# LissajousRevA.net
KiCad netlist of a schematic drawn in EAGLE
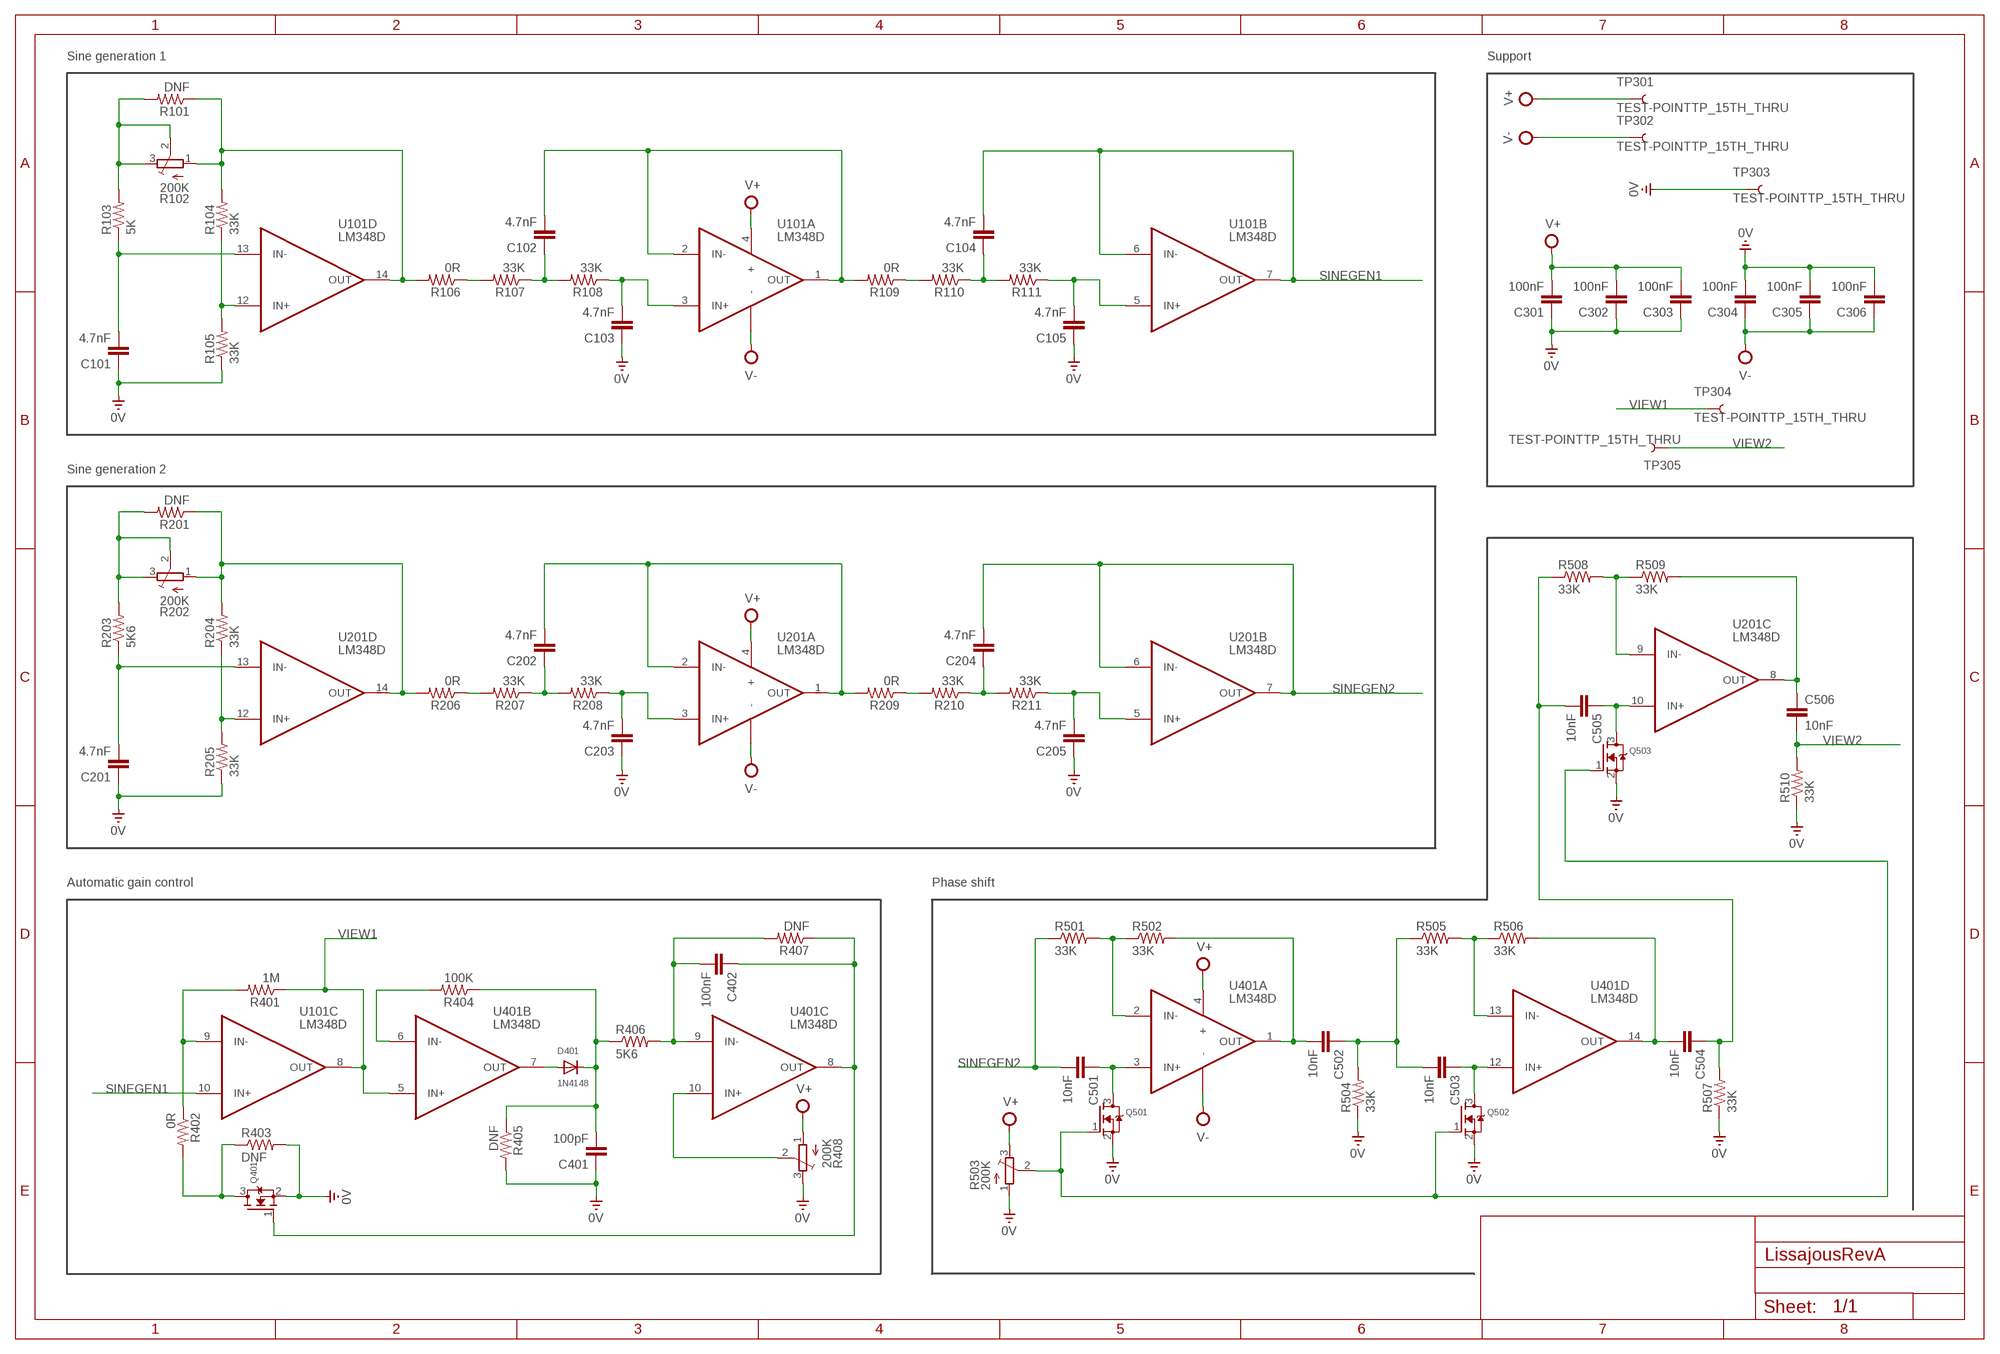
[diagram p0: schematic, sheet 1]

(export (version "E")
  (design (tool "Eeschema 10.0.6"))
  (components
    (comp (ref "C101")
      (value "4.7nF")
      (footprint "eagle-import:0603-CAP")
      (libsource (lib "eagle-import") (part "CAP0603-CAP"))
    )
    (comp (ref "C102")
      (value "4.7nF")
      (footprint "eagle-import:0603-CAP")
      (libsource (lib "eagle-import") (part "CAP0603-CAP"))
    )
    (comp (ref "C103")
      (value "4.7nF")
      (footprint "eagle-import:0603-CAP")
      (libsource (lib "eagle-import") (part "CAP0603-CAP"))
    )
    (comp (ref "C104")
      (value "4.7nF")
      (footprint "eagle-import:0603-CAP")
      (libsource (lib "eagle-import") (part "CAP0603-CAP"))
    )
    (comp (ref "C105")
      (value "4.7nF")
      (footprint "eagle-import:0603-CAP")
      (libsource (lib "eagle-import") (part "CAP0603-CAP"))
    )
    (comp (ref "C201")
      (value "4.7nF")
      (footprint "eagle-import:0603-CAP")
      (libsource (lib "eagle-import") (part "CAP0603-CAP"))
    )
    (comp (ref "C202")
      (value "4.7nF")
      (footprint "eagle-import:0603-CAP")
      (libsource (lib "eagle-import") (part "CAP0603-CAP"))
    )
    (comp (ref "C203")
      (value "4.7nF")
      (footprint "eagle-import:0603-CAP")
      (libsource (lib "eagle-import") (part "CAP0603-CAP"))
    )
    (comp (ref "C204")
      (value "4.7nF")
      (footprint "eagle-import:0603-CAP")
      (libsource (lib "eagle-import") (part "CAP0603-CAP"))
    )
    (comp (ref "C205")
      (value "4.7nF")
      (footprint "eagle-import:0603-CAP")
      (libsource (lib "eagle-import") (part "CAP0603-CAP"))
    )
    (comp (ref "C301")
      (value "100nF")
      (footprint "eagle-import:0603-CAP")
      (libsource (lib "eagle-import") (part "CAP0603-CAP"))
    )
    (comp (ref "C302")
      (value "100nF")
      (footprint "eagle-import:0603-CAP")
      (libsource (lib "eagle-import") (part "CAP0603-CAP"))
    )
    (comp (ref "C303")
      (value "100nF")
      (footprint "eagle-import:0603-CAP")
      (libsource (lib "eagle-import") (part "CAP0603-CAP"))
    )
    (comp (ref "C304")
      (value "100nF")
      (footprint "eagle-import:0603-CAP")
      (libsource (lib "eagle-import") (part "CAP0603-CAP"))
    )
    (comp (ref "C305")
      (value "100nF")
      (footprint "eagle-import:0603-CAP")
      (libsource (lib "eagle-import") (part "CAP0603-CAP"))
    )
    (comp (ref "C306")
      (value "100nF")
      (footprint "eagle-import:0603-CAP")
      (libsource (lib "eagle-import") (part "CAP0603-CAP"))
    )
    (comp (ref "C401")
      (value "100pF")
      (footprint "eagle-import:0603-CAP")
      (libsource (lib "eagle-import") (part "CAP0603-CAP"))
    )
    (comp (ref "C402")
      (value "100nF")
      (footprint "eagle-import:0603-CAP")
      (libsource (lib "eagle-import") (part "CAP0603-CAP"))
    )
    (comp (ref "C501")
      (value "10nF")
      (footprint "eagle-import:0603-CAP")
      (libsource (lib "eagle-import") (part "CAP0603-CAP"))
    )
    (comp (ref "C502")
      (value "10nF")
      (footprint "eagle-import:0603-CAP")
      (libsource (lib "eagle-import") (part "CAP0603-CAP"))
    )
    (comp (ref "C503")
      (value "10nF")
      (footprint "eagle-import:0603-CAP")
      (libsource (lib "eagle-import") (part "CAP0603-CAP"))
    )
    (comp (ref "C504")
      (value "10nF")
      (footprint "eagle-import:0603-CAP")
      (libsource (lib "eagle-import") (part "CAP0603-CAP"))
    )
    (comp (ref "C505")
      (value "10nF")
      (footprint "eagle-import:0603-CAP")
      (libsource (lib "eagle-import") (part "CAP0603-CAP"))
    )
    (comp (ref "C506")
      (value "10nF")
      (footprint "eagle-import:0603-CAP")
      (libsource (lib "eagle-import") (part "CAP0603-CAP"))
    )
    (comp (ref "D401")
      (value "1N4148")
      (footprint "eagle-import:SMADIODE")
      (libsource (lib "eagle-import") (part "DIODESMA"))
    )
    (comp (ref "Q401")
      (value "MOSFET-NREFLOW")
      (footprint "eagle-import:SOT23")
      (libsource (lib "eagle-import") (part "MOSFET-NREFLOW"))
    )
    (comp (ref "Q501")
      (value "MOSFET-NREFLOW")
      (footprint "eagle-import:SOT23")
      (libsource (lib "eagle-import") (part "MOSFET-NREFLOW"))
    )
    (comp (ref "Q502")
      (value "MOSFET-NREFLOW")
      (footprint "eagle-import:SOT23")
      (libsource (lib "eagle-import") (part "MOSFET-NREFLOW"))
    )
    (comp (ref "Q503")
      (value "MOSFET-NREFLOW")
      (footprint "eagle-import:SOT23")
      (libsource (lib "eagle-import") (part "MOSFET-NREFLOW"))
    )
    (comp (ref "R101")
      (value "DNF")
      (footprint "eagle-import:0603-RES")
      (libsource (lib "eagle-import") (part "RESISTOR0603-RES"))
    )
    (comp (ref "R102")
      (value "200K")
      (footprint "eagle-import:TC33X")
      (libsource (lib "eagle-import") (part "TRIMPOTTC33X"))
    )
    (comp (ref "R103")
      (value "5K")
      (footprint "eagle-import:0603-RES")
      (libsource (lib "eagle-import") (part "RESISTOR0603-RES"))
    )
    (comp (ref "R104")
      (value "33K")
      (footprint "eagle-import:0603-RES")
      (libsource (lib "eagle-import") (part "RESISTOR0603-RES"))
    )
    (comp (ref "R105")
      (value "33K")
      (footprint "eagle-import:0603-RES")
      (libsource (lib "eagle-import") (part "RESISTOR0603-RES"))
    )
    (comp (ref "R106")
      (value "0R")
      (footprint "eagle-import:0603-RES")
      (libsource (lib "eagle-import") (part "RESISTOR0603-RES"))
    )
    (comp (ref "R107")
      (value "33K")
      (footprint "eagle-import:0603-RES")
      (libsource (lib "eagle-import") (part "RESISTOR0603-RES"))
    )
    (comp (ref "R108")
      (value "33K")
      (footprint "eagle-import:0603-RES")
      (libsource (lib "eagle-import") (part "RESISTOR0603-RES"))
    )
    (comp (ref "R109")
      (value "0R")
      (footprint "eagle-import:0603-RES")
      (libsource (lib "eagle-import") (part "RESISTOR0603-RES"))
    )
    (comp (ref "R110")
      (value "33K")
      (footprint "eagle-import:0603-RES")
      (libsource (lib "eagle-import") (part "RESISTOR0603-RES"))
    )
    (comp (ref "R111")
      (value "33K")
      (footprint "eagle-import:0603-RES")
      (libsource (lib "eagle-import") (part "RESISTOR0603-RES"))
    )
    (comp (ref "R201")
      (value "DNF")
      (footprint "eagle-import:0603-RES")
      (libsource (lib "eagle-import") (part "RESISTOR0603-RES"))
    )
    (comp (ref "R202")
      (value "200K")
      (footprint "eagle-import:TC33X")
      (libsource (lib "eagle-import") (part "TRIMPOTTC33X"))
    )
    (comp (ref "R203")
      (value "5K6")
      (footprint "eagle-import:0603-RES")
      (libsource (lib "eagle-import") (part "RESISTOR0603-RES"))
    )
    (comp (ref "R204")
      (value "33K")
      (footprint "eagle-import:0603-RES")
      (libsource (lib "eagle-import") (part "RESISTOR0603-RES"))
    )
    (comp (ref "R205")
      (value "33K")
      (footprint "eagle-import:0603-RES")
      (libsource (lib "eagle-import") (part "RESISTOR0603-RES"))
    )
    (comp (ref "R206")
      (value "0R")
      (footprint "eagle-import:0603-RES")
      (libsource (lib "eagle-import") (part "RESISTOR0603-RES"))
    )
    (comp (ref "R207")
      (value "33K")
      (footprint "eagle-import:0603-RES")
      (libsource (lib "eagle-import") (part "RESISTOR0603-RES"))
    )
    (comp (ref "R208")
      (value "33K")
      (footprint "eagle-import:0603-RES")
      (libsource (lib "eagle-import") (part "RESISTOR0603-RES"))
    )
    (comp (ref "R209")
      (value "0R")
      (footprint "eagle-import:0603-RES")
      (libsource (lib "eagle-import") (part "RESISTOR0603-RES"))
    )
    (comp (ref "R210")
      (value "33K")
      (footprint "eagle-import:0603-RES")
      (libsource (lib "eagle-import") (part "RESISTOR0603-RES"))
    )
    (comp (ref "R211")
      (value "33K")
      (footprint "eagle-import:0603-RES")
      (libsource (lib "eagle-import") (part "RESISTOR0603-RES"))
    )
    (comp (ref "R401")
      (value "1M")
      (footprint "eagle-import:0603-RES")
      (libsource (lib "eagle-import") (part "RESISTOR0603-RES"))
    )
    (comp (ref "R402")
      (value "0R")
      (footprint "eagle-import:0603-RES")
      (libsource (lib "eagle-import") (part "RESISTOR0603-RES"))
    )
    (comp (ref "R403")
      (value "DNF")
      (footprint "eagle-import:0603-RES")
      (libsource (lib "eagle-import") (part "RESISTOR0603-RES"))
    )
    (comp (ref "R404")
      (value "100K")
      (footprint "eagle-import:0603-RES")
      (libsource (lib "eagle-import") (part "RESISTOR0603-RES"))
    )
    (comp (ref "R405")
      (value "DNF")
      (footprint "eagle-import:0603-RES")
      (libsource (lib "eagle-import") (part "RESISTOR0603-RES"))
    )
    (comp (ref "R406")
      (value "5K6")
      (footprint "eagle-import:0603-RES")
      (libsource (lib "eagle-import") (part "RESISTOR0603-RES"))
    )
    (comp (ref "R407")
      (value "DNF")
      (footprint "eagle-import:0603-RES")
      (libsource (lib "eagle-import") (part "RESISTOR0603-RES"))
    )
    (comp (ref "R408")
      (value "200K")
      (footprint "eagle-import:TC33X")
      (libsource (lib "eagle-import") (part "TRIMPOTTC33X"))
    )
    (comp (ref "R501")
      (value "33K")
      (footprint "eagle-import:0603-RES")
      (libsource (lib "eagle-import") (part "RESISTOR0603-RES"))
    )
    (comp (ref "R502")
      (value "33K")
      (footprint "eagle-import:0603-RES")
      (libsource (lib "eagle-import") (part "RESISTOR0603-RES"))
    )
    (comp (ref "R503")
      (value "200K")
      (footprint "eagle-import:TC33X")
      (libsource (lib "eagle-import") (part "TRIMPOTTC33X"))
    )
    (comp (ref "R504")
      (value "33K")
      (footprint "eagle-import:0603-RES")
      (libsource (lib "eagle-import") (part "RESISTOR0603-RES"))
    )
    (comp (ref "R505")
      (value "33K")
      (footprint "eagle-import:0603-RES")
      (libsource (lib "eagle-import") (part "RESISTOR0603-RES"))
    )
    (comp (ref "R506")
      (value "33K")
      (footprint "eagle-import:0603-RES")
      (libsource (lib "eagle-import") (part "RESISTOR0603-RES"))
    )
    (comp (ref "R507")
      (value "33K")
      (footprint "eagle-import:0603-RES")
      (libsource (lib "eagle-import") (part "RESISTOR0603-RES"))
    )
    (comp (ref "R508")
      (value "33K")
      (footprint "eagle-import:0603-RES")
      (libsource (lib "eagle-import") (part "RESISTOR0603-RES"))
    )
    (comp (ref "R509")
      (value "33K")
      (footprint "eagle-import:0603-RES")
      (libsource (lib "eagle-import") (part "RESISTOR0603-RES"))
    )
    (comp (ref "R510")
      (value "33K")
      (footprint "eagle-import:0603-RES")
      (libsource (lib "eagle-import") (part "RESISTOR0603-RES"))
    )
    (comp (ref "TP301")
      (value "TEST-POINTTP_15TH_THRU")
      (footprint "eagle-import:TP_15TH")
      (libsource (lib "eagle-import") (part "TEST-POINTTP_15TH_THRU"))
    )
    (comp (ref "TP302")
      (value "TEST-POINTTP_15TH_THRU")
      (footprint "eagle-import:TP_15TH")
      (libsource (lib "eagle-import") (part "TEST-POINTTP_15TH_THRU"))
    )
    (comp (ref "TP303")
      (value "TEST-POINTTP_15TH_THRU")
      (footprint "eagle-import:TP_15TH")
      (libsource (lib "eagle-import") (part "TEST-POINTTP_15TH_THRU"))
    )
    (comp (ref "TP304")
      (value "TEST-POINTTP_15TH_THRU")
      (footprint "eagle-import:TP_15TH")
      (libsource (lib "eagle-import") (part "TEST-POINTTP_15TH_THRU"))
    )
    (comp (ref "TP305")
      (value "TEST-POINTTP_15TH_THRU")
      (footprint "eagle-import:TP_15TH")
      (libsource (lib "eagle-import") (part "TEST-POINTTP_15TH_THRU"))
    )
    (comp (ref "U101")
      (value "LM348D")
      (footprint "eagle-import:SOIC127P600X175-14N")
      (libsource (lib "eagle-import") (part "LM348D"))
    )
    (comp (ref "U201")
      (value "LM348D")
      (footprint "eagle-import:SOIC127P600X175-14N")
      (libsource (lib "eagle-import") (part "LM348D"))
    )
    (comp (ref "U401")
      (value "LM348D")
      (footprint "eagle-import:SOIC127P600X175-14N")
      (libsource (lib "eagle-import") (part "LM348D"))
    )
  )
  (nets
    (net (code "1") (name "/SINEGEN1") (class "Default")
      (node (ref "C104") (pin "2") (pinfunction "2_2") (pintype "passive"))
      (node (ref "U101") (pin "10") (pinfunction "IN+_10") (pintype "output"))
      (node (ref "U101") (pin "6") (pinfunction "IN-_6") (pintype "output"))
      (node (ref "U101") (pin "7") (pinfunction "OUT_7") (pintype "output"))
    )
    (net (code "2") (name "/SINEGEN2") (class "Default")
      (node (ref "C204") (pin "2") (pinfunction "2_2") (pintype "passive"))
      (node (ref "C501") (pin "2") (pinfunction "2_2") (pintype "passive"))
      (node (ref "R501") (pin "1") (pinfunction "1_1") (pintype "passive"))
      (node (ref "U201") (pin "6") (pinfunction "IN-_6") (pintype "output"))
      (node (ref "U201") (pin "7") (pinfunction "OUT_7") (pintype "output"))
    )
    (net (code "3") (name "/VIEW1") (class "Default")
      (node (ref "R401") (pin "1") (pinfunction "1_1") (pintype "passive"))
      (node (ref "TP304") (pin "P$1") (pinfunction "1_P$1") (pintype "bidirectional"))
      (node (ref "U101") (pin "8") (pinfunction "OUT_8") (pintype "output"))
      (node (ref "U401") (pin "5") (pinfunction "IN+_5") (pintype "output"))
    )
    (net (code "4") (name "/VIEW2") (class "Default")
      (node (ref "C506") (pin "2") (pinfunction "2_2") (pintype "passive"))
      (node (ref "R510") (pin "2") (pinfunction "2_2") (pintype "passive"))
      (node (ref "TP305") (pin "P$1") (pinfunction "1_P$1") (pintype "bidirectional"))
    )
    (net (code "5") (name "0V") (class "Default")
      (node (ref "C101") (pin "1") (pinfunction "1_1") (pintype "passive"))
      (node (ref "C103") (pin "1") (pinfunction "1_1") (pintype "passive"))
      (node (ref "C105") (pin "1") (pinfunction "1_1") (pintype "passive"))
      (node (ref "C201") (pin "1") (pinfunction "1_1") (pintype "passive"))
      (node (ref "C203") (pin "1") (pinfunction "1_1") (pintype "passive"))
      (node (ref "C205") (pin "1") (pinfunction "1_1") (pintype "passive"))
      (node (ref "C301") (pin "1") (pinfunction "1_1") (pintype "passive"))
      (node (ref "C302") (pin "1") (pinfunction "1_1") (pintype "passive"))
      (node (ref "C303") (pin "1") (pinfunction "1_1") (pintype "passive"))
      (node (ref "C304") (pin "2") (pinfunction "2_2") (pintype "passive"))
      (node (ref "C305") (pin "2") (pinfunction "2_2") (pintype "passive"))
      (node (ref "C306") (pin "2") (pinfunction "2_2") (pintype "passive"))
      (node (ref "C401") (pin "1") (pinfunction "1_1") (pintype "passive"))
      (node (ref "Q401") (pin "2") (pinfunction "S_2") (pintype "bidirectional"))
      (node (ref "Q501") (pin "2") (pinfunction "S_2") (pintype "bidirectional"))
      (node (ref "Q502") (pin "2") (pinfunction "S_2") (pintype "bidirectional"))
      (node (ref "Q503") (pin "2") (pinfunction "S_2") (pintype "bidirectional"))
      (node (ref "R105") (pin "1") (pinfunction "1_1") (pintype "passive"))
      (node (ref "R205") (pin "1") (pinfunction "1_1") (pintype "passive"))
      (node (ref "R403") (pin "2") (pinfunction "2_2") (pintype "passive"))
      (node (ref "R405") (pin "2") (pinfunction "2_2") (pintype "passive"))
      (node (ref "R408") (pin "3") (pinfunction "E_3") (pintype "passive"))
      (node (ref "R503") (pin "1") (pinfunction "A_1") (pintype "passive"))
      (node (ref "R504") (pin "1") (pinfunction "1_1") (pintype "passive"))
      (node (ref "R507") (pin "1") (pinfunction "1_1") (pintype "passive"))
      (node (ref "R510") (pin "1") (pinfunction "1_1") (pintype "passive"))
      (node (ref "TP303") (pin "P$1") (pinfunction "1_P$1") (pintype "bidirectional"))
    )
    (net (code "6") (name "Net-(C102-Pad1)") (class "Default")
      (node (ref "C102") (pin "1") (pinfunction "1_1") (pintype "passive"))
      (node (ref "R107") (pin "1") (pinfunction "1_1") (pintype "passive"))
      (node (ref "R108") (pin "2") (pinfunction "2_2") (pintype "passive"))
    )
    (net (code "7") (name "Net-(C104-Pad1)") (class "Default")
      (node (ref "C104") (pin "1") (pinfunction "1_1") (pintype "passive"))
      (node (ref "R110") (pin "1") (pinfunction "1_1") (pintype "passive"))
      (node (ref "R111") (pin "2") (pinfunction "2_2") (pintype "passive"))
    )
    (net (code "8") (name "Net-(C202-Pad1)") (class "Default")
      (node (ref "C202") (pin "1") (pinfunction "1_1") (pintype "passive"))
      (node (ref "R207") (pin "1") (pinfunction "1_1") (pintype "passive"))
      (node (ref "R208") (pin "2") (pinfunction "2_2") (pintype "passive"))
    )
    (net (code "9") (name "Net-(C204-Pad1)") (class "Default")
      (node (ref "C204") (pin "1") (pinfunction "1_1") (pintype "passive"))
      (node (ref "R210") (pin "1") (pinfunction "1_1") (pintype "passive"))
      (node (ref "R211") (pin "2") (pinfunction "2_2") (pintype "passive"))
    )
    (net (code "10") (name "Net-(C401-Pad2)") (class "Default")
      (node (ref "C401") (pin "2") (pinfunction "2_2") (pintype "passive"))
      (node (ref "D401") (pin "C") (pinfunction "C_C") (pintype "passive"))
      (node (ref "R404") (pin "1") (pinfunction "1_1") (pintype "passive"))
      (node (ref "R405") (pin "1") (pinfunction "1_1") (pintype "passive"))
      (node (ref "R406") (pin "1") (pinfunction "1_1") (pintype "passive"))
    )
    (net (code "11") (name "Net-(C502-Pad1)") (class "Default")
      (node (ref "C502") (pin "1") (pinfunction "1_1") (pintype "passive"))
      (node (ref "C503") (pin "2") (pinfunction "2_2") (pintype "passive"))
      (node (ref "R504") (pin "2") (pinfunction "2_2") (pintype "passive"))
      (node (ref "R505") (pin "1") (pinfunction "1_1") (pintype "passive"))
    )
    (net (code "12") (name "Net-(C504-Pad1)") (class "Default")
      (node (ref "C504") (pin "1") (pinfunction "1_1") (pintype "passive"))
      (node (ref "C505") (pin "2") (pinfunction "2_2") (pintype "passive"))
      (node (ref "R507") (pin "2") (pinfunction "2_2") (pintype "passive"))
      (node (ref "R508") (pin "1") (pinfunction "1_1") (pintype "passive"))
    )
    (net (code "13") (name "Net-(Q401-D)") (class "Default")
      (node (ref "Q401") (pin "3") (pinfunction "D_3") (pintype "bidirectional"))
      (node (ref "R402") (pin "2") (pinfunction "2_2") (pintype "passive"))
      (node (ref "R403") (pin "1") (pinfunction "1_1") (pintype "passive"))
    )
    (net (code "14") (name "Net-(Q401-G)") (class "Default")
      (node (ref "C402") (pin "1") (pinfunction "1_1") (pintype "passive"))
      (node (ref "Q401") (pin "1") (pinfunction "G_1") (pintype "bidirectional"))
      (node (ref "R407") (pin "1") (pinfunction "1_1") (pintype "passive"))
      (node (ref "U401") (pin "8") (pinfunction "OUT_8") (pintype "output"))
    )
    (net (code "15") (name "Net-(Q501-D)") (class "Default")
      (node (ref "C501") (pin "1") (pinfunction "1_1") (pintype "passive"))
      (node (ref "Q501") (pin "3") (pinfunction "D_3") (pintype "bidirectional"))
      (node (ref "U401") (pin "3") (pinfunction "IN+_3") (pintype "output"))
    )
    (net (code "16") (name "Net-(Q501-G)") (class "Default")
      (node (ref "Q501") (pin "1") (pinfunction "G_1") (pintype "bidirectional"))
      (node (ref "Q502") (pin "1") (pinfunction "G_1") (pintype "bidirectional"))
      (node (ref "Q503") (pin "1") (pinfunction "G_1") (pintype "bidirectional"))
      (node (ref "R503") (pin "2") (pinfunction "S_2") (pintype "passive"))
    )
    (net (code "17") (name "Net-(Q502-D)") (class "Default")
      (node (ref "C503") (pin "1") (pinfunction "1_1") (pintype "passive"))
      (node (ref "Q502") (pin "3") (pinfunction "D_3") (pintype "bidirectional"))
      (node (ref "U401") (pin "12") (pinfunction "IN+_12") (pintype "output"))
    )
    (net (code "18") (name "Net-(Q503-D)") (class "Default")
      (node (ref "C505") (pin "1") (pinfunction "1_1") (pintype "passive"))
      (node (ref "Q503") (pin "3") (pinfunction "D_3") (pintype "bidirectional"))
      (node (ref "U201") (pin "10") (pinfunction "IN+_10") (pintype "output"))
    )
    (net (code "19") (name "Net-(R102-A)") (class "Default")
      (node (ref "R101") (pin "1") (pinfunction "1_1") (pintype "passive"))
      (node (ref "R102") (pin "1") (pinfunction "A_1") (pintype "passive"))
      (node (ref "R104") (pin "2") (pinfunction "2_2") (pintype "passive"))
      (node (ref "R106") (pin "2") (pinfunction "2_2") (pintype "passive"))
      (node (ref "U101") (pin "14") (pinfunction "OUT_14") (pintype "output"))
    )
    (net (code "20") (name "Net-(R102-E)") (class "Default")
      (node (ref "R101") (pin "2") (pinfunction "2_2") (pintype "passive"))
      (node (ref "R102") (pin "2") (pinfunction "S_2") (pintype "passive"))
      (node (ref "R102") (pin "3") (pinfunction "E_3") (pintype "passive"))
      (node (ref "R103") (pin "2") (pinfunction "2_2") (pintype "passive"))
    )
    (net (code "21") (name "Net-(R106-Pad1)") (class "Default")
      (node (ref "R106") (pin "1") (pinfunction "1_1") (pintype "passive"))
      (node (ref "R107") (pin "2") (pinfunction "2_2") (pintype "passive"))
    )
    (net (code "22") (name "Net-(R109-Pad1)") (class "Default")
      (node (ref "R109") (pin "1") (pinfunction "1_1") (pintype "passive"))
      (node (ref "R110") (pin "2") (pinfunction "2_2") (pintype "passive"))
    )
    (net (code "23") (name "Net-(R202-A)") (class "Default")
      (node (ref "R201") (pin "1") (pinfunction "1_1") (pintype "passive"))
      (node (ref "R202") (pin "1") (pinfunction "A_1") (pintype "passive"))
      (node (ref "R204") (pin "2") (pinfunction "2_2") (pintype "passive"))
      (node (ref "R206") (pin "2") (pinfunction "2_2") (pintype "passive"))
      (node (ref "U201") (pin "14") (pinfunction "OUT_14") (pintype "output"))
    )
    (net (code "24") (name "Net-(R202-E)") (class "Default")
      (node (ref "R201") (pin "2") (pinfunction "2_2") (pintype "passive"))
      (node (ref "R202") (pin "2") (pinfunction "S_2") (pintype "passive"))
      (node (ref "R202") (pin "3") (pinfunction "E_3") (pintype "passive"))
      (node (ref "R203") (pin "2") (pinfunction "2_2") (pintype "passive"))
    )
    (net (code "25") (name "Net-(R206-Pad1)") (class "Default")
      (node (ref "R206") (pin "1") (pinfunction "1_1") (pintype "passive"))
      (node (ref "R207") (pin "2") (pinfunction "2_2") (pintype "passive"))
    )
    (net (code "26") (name "Net-(R209-Pad1)") (class "Default")
      (node (ref "R209") (pin "1") (pinfunction "1_1") (pintype "passive"))
      (node (ref "R210") (pin "2") (pinfunction "2_2") (pintype "passive"))
    )
    (net (code "27") (name "Net-(R408-S)") (class "Default")
      (node (ref "R408") (pin "2") (pinfunction "S_2") (pintype "passive"))
      (node (ref "U401") (pin "10") (pinfunction "IN+_10") (pintype "output"))
    )
    (net (code "28") (name "Net-(U101A-IN+)") (class "Default")
      (node (ref "C103") (pin "2") (pinfunction "2_2") (pintype "passive"))
      (node (ref "R108") (pin "1") (pinfunction "1_1") (pintype "passive"))
      (node (ref "U101") (pin "3") (pinfunction "IN+_3") (pintype "output"))
    )
    (net (code "29") (name "Net-(U101A-IN-)") (class "Default")
      (node (ref "C102") (pin "2") (pinfunction "2_2") (pintype "passive"))
      (node (ref "R109") (pin "2") (pinfunction "2_2") (pintype "passive"))
      (node (ref "U101") (pin "1") (pinfunction "OUT_1") (pintype "output"))
      (node (ref "U101") (pin "2") (pinfunction "IN-_2") (pintype "output"))
    )
    (net (code "30") (name "Net-(U101B-IN+)") (class "Default")
      (node (ref "C105") (pin "2") (pinfunction "2_2") (pintype "passive"))
      (node (ref "R111") (pin "1") (pinfunction "1_1") (pintype "passive"))
      (node (ref "U101") (pin "5") (pinfunction "IN+_5") (pintype "output"))
    )
    (net (code "31") (name "Net-(U101C-IN-)") (class "Default")
      (node (ref "R401") (pin "2") (pinfunction "2_2") (pintype "passive"))
      (node (ref "R402") (pin "1") (pinfunction "1_1") (pintype "passive"))
      (node (ref "U101") (pin "9") (pinfunction "IN-_9") (pintype "output"))
    )
    (net (code "32") (name "Net-(U101D-IN+)") (class "Default")
      (node (ref "R104") (pin "1") (pinfunction "1_1") (pintype "passive"))
      (node (ref "R105") (pin "2") (pinfunction "2_2") (pintype "passive"))
      (node (ref "U101") (pin "12") (pinfunction "IN+_12") (pintype "output"))
    )
    (net (code "33") (name "Net-(U101D-IN-)") (class "Default")
      (node (ref "C101") (pin "2") (pinfunction "2_2") (pintype "passive"))
      (node (ref "R103") (pin "1") (pinfunction "1_1") (pintype "passive"))
      (node (ref "U101") (pin "13") (pinfunction "IN-_13") (pintype "output"))
    )
    (net (code "34") (name "Net-(U201A-IN+)") (class "Default")
      (node (ref "C203") (pin "2") (pinfunction "2_2") (pintype "passive"))
      (node (ref "R208") (pin "1") (pinfunction "1_1") (pintype "passive"))
      (node (ref "U201") (pin "3") (pinfunction "IN+_3") (pintype "output"))
    )
    (net (code "35") (name "Net-(U201A-IN-)") (class "Default")
      (node (ref "C202") (pin "2") (pinfunction "2_2") (pintype "passive"))
      (node (ref "R209") (pin "2") (pinfunction "2_2") (pintype "passive"))
      (node (ref "U201") (pin "1") (pinfunction "OUT_1") (pintype "output"))
      (node (ref "U201") (pin "2") (pinfunction "IN-_2") (pintype "output"))
    )
    (net (code "36") (name "Net-(U201B-IN+)") (class "Default")
      (node (ref "C205") (pin "2") (pinfunction "2_2") (pintype "passive"))
      (node (ref "R211") (pin "1") (pinfunction "1_1") (pintype "passive"))
      (node (ref "U201") (pin "5") (pinfunction "IN+_5") (pintype "output"))
    )
    (net (code "37") (name "Net-(U201C-IN-)") (class "Default")
      (node (ref "R508") (pin "2") (pinfunction "2_2") (pintype "passive"))
      (node (ref "R509") (pin "1") (pinfunction "1_1") (pintype "passive"))
      (node (ref "U201") (pin "9") (pinfunction "IN-_9") (pintype "output"))
    )
    (net (code "38") (name "Net-(U201C-OUT)") (class "Default")
      (node (ref "C506") (pin "1") (pinfunction "1_1") (pintype "passive"))
      (node (ref "R509") (pin "2") (pinfunction "2_2") (pintype "passive"))
      (node (ref "U201") (pin "8") (pinfunction "OUT_8") (pintype "output"))
    )
    (net (code "39") (name "Net-(U201D-IN+)") (class "Default")
      (node (ref "R204") (pin "1") (pinfunction "1_1") (pintype "passive"))
      (node (ref "R205") (pin "2") (pinfunction "2_2") (pintype "passive"))
      (node (ref "U201") (pin "12") (pinfunction "IN+_12") (pintype "output"))
    )
    (net (code "40") (name "Net-(U201D-IN-)") (class "Default")
      (node (ref "C201") (pin "2") (pinfunction "2_2") (pintype "passive"))
      (node (ref "R203") (pin "1") (pinfunction "1_1") (pintype "passive"))
      (node (ref "U201") (pin "13") (pinfunction "IN-_13") (pintype "output"))
    )
    (net (code "41") (name "Net-(U401A-IN-)") (class "Default")
      (node (ref "R501") (pin "2") (pinfunction "2_2") (pintype "passive"))
      (node (ref "R502") (pin "1") (pinfunction "1_1") (pintype "passive"))
      (node (ref "U401") (pin "2") (pinfunction "IN-_2") (pintype "output"))
    )
    (net (code "42") (name "Net-(U401A-OUT)") (class "Default")
      (node (ref "C502") (pin "2") (pinfunction "2_2") (pintype "passive"))
      (node (ref "R502") (pin "2") (pinfunction "2_2") (pintype "passive"))
      (node (ref "U401") (pin "1") (pinfunction "OUT_1") (pintype "output"))
    )
    (net (code "43") (name "Net-(U401B-IN-)") (class "Default")
      (node (ref "R404") (pin "2") (pinfunction "2_2") (pintype "passive"))
      (node (ref "U401") (pin "6") (pinfunction "IN-_6") (pintype "output"))
    )
    (net (code "44") (name "Net-(U401B-OUT)") (class "Default")
      (node (ref "D401") (pin "A") (pinfunction "A_A") (pintype "passive"))
      (node (ref "U401") (pin "7") (pinfunction "OUT_7") (pintype "output"))
    )
    (net (code "45") (name "Net-(U401C-IN-)") (class "Default")
      (node (ref "C402") (pin "2") (pinfunction "2_2") (pintype "passive"))
      (node (ref "R406") (pin "2") (pinfunction "2_2") (pintype "passive"))
      (node (ref "R407") (pin "2") (pinfunction "2_2") (pintype "passive"))
      (node (ref "U401") (pin "9") (pinfunction "IN-_9") (pintype "output"))
    )
    (net (code "46") (name "Net-(U401D-IN-)") (class "Default")
      (node (ref "R505") (pin "2") (pinfunction "2_2") (pintype "passive"))
      (node (ref "R506") (pin "1") (pinfunction "1_1") (pintype "passive"))
      (node (ref "U401") (pin "13") (pinfunction "IN-_13") (pintype "output"))
    )
    (net (code "47") (name "Net-(U401D-OUT)") (class "Default")
      (node (ref "C504") (pin "2") (pinfunction "2_2") (pintype "passive"))
      (node (ref "R506") (pin "2") (pinfunction "2_2") (pintype "passive"))
      (node (ref "U401") (pin "14") (pinfunction "OUT_14") (pintype "output"))
    )
    (net (code "48") (name "V+") (class "Default")
      (node (ref "C301") (pin "2") (pinfunction "2_2") (pintype "passive"))
      (node (ref "C302") (pin "2") (pinfunction "2_2") (pintype "passive"))
      (node (ref "C303") (pin "2") (pinfunction "2_2") (pintype "passive"))
      (node (ref "R408") (pin "1") (pinfunction "A_1") (pintype "passive"))
      (node (ref "R503") (pin "3") (pinfunction "E_3") (pintype "passive"))
      (node (ref "TP301") (pin "P$1") (pinfunction "1_P$1") (pintype "bidirectional"))
      (node (ref "U101") (pin "4") (pinfunction "+_4") (pintype "output"))
      (node (ref "U201") (pin "4") (pinfunction "+_4") (pintype "output"))
      (node (ref "U401") (pin "4") (pinfunction "+_4") (pintype "output"))
    )
    (net (code "49") (name "V-") (class "Default")
      (node (ref "C304") (pin "1") (pinfunction "1_1") (pintype "passive"))
      (node (ref "C305") (pin "1") (pinfunction "1_1") (pintype "passive"))
      (node (ref "C306") (pin "1") (pinfunction "1_1") (pintype "passive"))
      (node (ref "TP302") (pin "P$1") (pinfunction "1_P$1") (pintype "bidirectional"))
      (node (ref "U101") (pin "11") (pinfunction "-_11") (pintype "output"))
      (node (ref "U201") (pin "11") (pinfunction "-_11") (pintype "output"))
      (node (ref "U401") (pin "11") (pinfunction "-_11") (pintype "output"))
    )
  )
)
